# External_Camera_HAT_Connectors.net
KiCad netlist of a schematic drawn in Altium Designer
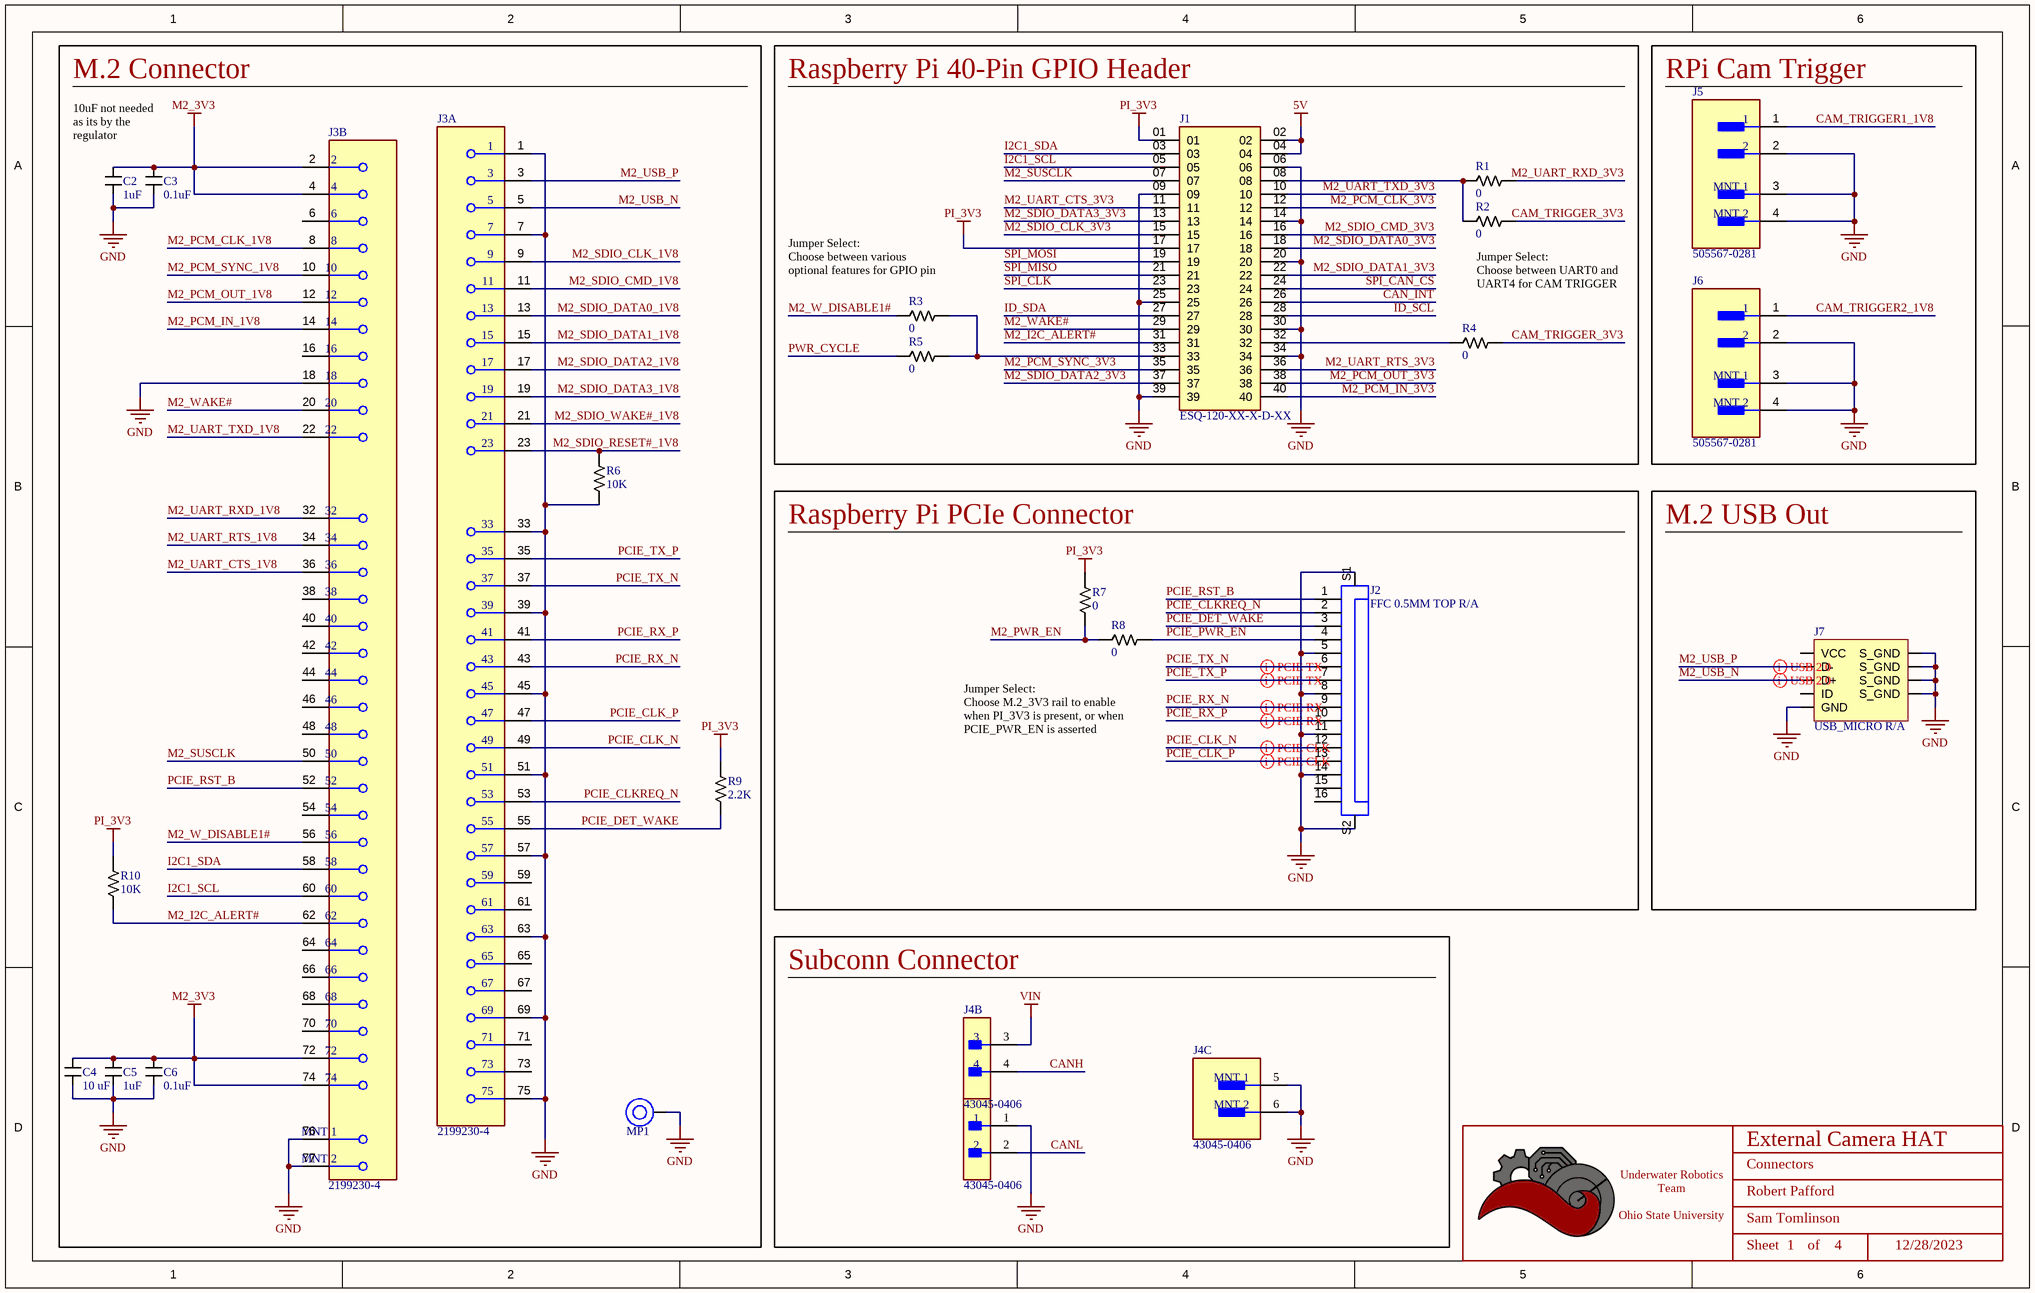
[diagram p0: External_Camera_HAT_Connectors.SchDoc]

(export (version "E")
  (design (tool "Eeschema 10.0.6"))
  (components
    (comp (ref "C2")
      (value "1uF")
      (footprint "CAPACITOR_0402")
      (description "Cap 1uF 16V +/-10%\r\nCeramic 0402")
      (fields
        (field (name "TOLERANCE") "+/- 10%")
        (field (name "VOLTAGE") "16V")
        (field (name "MADE BY") "Robert Pafford")
      )
      (libsource (lib "Capacitors") (part "CAPACITOR_1uF_0402"))
    )
    (comp (ref "C3")
      (value "0.1uF")
      (footprint "CAPACITOR_0402")
      (description "Cap 100nF 25V +/-10%\r\nCeramic 0402")
      (fields
        (field (name "TOLERANCE") "+/- 10%")
        (field (name "VOLTAGE") "25V")
        (field (name "MADE BY") "Robert Pafford")
      )
      (libsource (lib "Capacitors") (part "CAPACITOR_0.1uF_0402"))
    )
    (comp (ref "C4")
      (value "10uF Ceramic 6.3V")
      (footprint "CAPACITOR_0603")
      (description "Cap 10uF 6.3V +/-20%\r\nCeramic 0603")
      (fields
        (field (name "TOLERANCE") "+/- 20%")
        (field (name "VOLTAGE") "6.3V")
        (field (name "VALUE (UF)") "10 uF")
        (field (name "MADE BY") "Flip B")
      )
      (libsource (lib "Capacitors") (part "CAPACITOR_10uF_0603"))
    )
    (comp (ref "C5")
      (value "1uF")
      (footprint "CAPACITOR_0402")
      (description "Cap 1uF 16V +/-10%\r\nCeramic 0402")
      (fields
        (field (name "TOLERANCE") "+/- 10%")
        (field (name "VOLTAGE") "16V")
        (field (name "MADE BY") "Robert Pafford")
      )
      (libsource (lib "Capacitors") (part "CAPACITOR_1uF_0402"))
    )
    (comp (ref "C6")
      (value "0.1uF")
      (footprint "CAPACITOR_0402")
      (description "Cap 100nF 25V +/-10%\r\nCeramic 0402")
      (fields
        (field (name "TOLERANCE") "+/- 10%")
        (field (name "VOLTAGE") "25V")
        (field (name "MADE BY") "Robert Pafford")
      )
      (libsource (lib "Capacitors") (part "CAPACITOR_0.1uF_0402"))
    )
    (comp (ref "J1")
      (value "ESQ-120-XX-X-D-XX")
      (footprint "SAMTEC_ESQ-120-XX-X-D-XX")
      (description "ESQ - Samtec 2.54mm Elevated Dual Row Socket Strip 7.36mm Contact. 11.05mm Profile (13)")
      (fields (field (name "MP") "ESQ-120-13-L-D") (field (name "MF") "Samtec"))
      (libsource (lib "Connectors") (part "ESQ-120-XX-X-D-XX"))
    )
    (comp (ref "J2")
      (value "FFC 0.5MM TOP R/A")
      (footprint "FH12A-16S-0.5SH(55)")
      (description "16 Position FPC Connector Contacts, Top 0.02\" (0.5mm) Surface Mount, Right Angle, Gold Contacts")
      (fields (field (name "MADE BY") "Robert Pafford"))
      (libsource (lib "Connectors") (part "FFC_16POS_0.5MM_R/A_TOP"))
    )
    (comp (ref "J3")
      (value "2199230-4")
      (footprint "FP-2199230-4-MFG")
      (description "CONN FEMALE 67POS 0.020 GOLD")
      (fields
        (field (name "MANUFACTURER") "TE Connectivity")
        (field (name "OCTOPART") "https://octopart.com/2199230-4-te+connectivity-46436156")
      )
      (libsource (lib "Altium Content Vault") (part "6b4bc9aaecd91677fa565b830470f16"))
    )
    (comp (ref "J4")
      (value "43045-0406")
      (footprint "FP-43045-0406-MFG")
      (description "CONN HEADER SMD R/A 4POS 3MM")
      (libsource (lib "Altium Content Vault") (part "58585532e1459b3b5fa8464169874db"))
    )
    (comp (ref "J5")
      (value "505567-0281")
      (footprint "FP-505567-0281-MFG")
      (description "CONN HEADER SMD R/A 2POS 1.25MM")
      (libsource (lib "Altium Content Vault") (part "56ec3178a87b3978bdc1b3682cd516a"))
    )
    (comp (ref "J6")
      (value "505567-0281")
      (footprint "FP-505567-0281-MFG")
      (description "CONN HEADER SMD R/A 2POS 1.25MM")
      (libsource (lib "Altium Content Vault") (part "56ec3178a87b3978bdc1b3682cd516a"))
    )
    (comp (ref "J7")
      (value "USB_MICRO R/A")
      (footprint "CONN_MINIUSB")
      (description "Amphenol Micro USB-B\r\nUSB2.0 5 Pin Right Angle SMD")
      (fields (field (name "MANUFACTURER") "Amphenol") (field (name "CREATED BY") "Flip B"))
      (libsource (lib "Connectors") (part "CONN_MICROUSB"))
    )
    (comp (ref "MP1")
      (value "M3 x 2.5mm")
      (footprint "78614025360")
      (description "WE-SMSA SMT Spacer Studs Automotive, OD 6mm, ID 4.2mm, M3 x 2.5mm")
      (fields
        (field (name "MANUFACTURER PART NUMBER") "78614025360")
        (field (name "MANUFACTURER") "Wurth Elektronik")
      )
      (libsource (lib "Connectors") (part "M3_STANDOFF_78614025360"))
    )
    (comp (ref "R1")
      (value "0 Ohm 1% 1/16W")
      (footprint "RESISTOR_0402")
      (description "RES 0 OHM 1% 1/16W 0402")
      (fields
        (field (name "TOLERANCE") "+/- 1%")
        (field (name "VALUE  (OHMS)") "0")
        (field (name "MADE BY") "Robert Pafford")
      )
      (libsource (lib "Resistors") (part "RESISTOR_0_0402"))
    )
    (comp (ref "R2")
      (value "0 Ohm 1% 1/16W")
      (footprint "RESISTOR_0402")
      (description "RES 0 OHM 1% 1/16W 0402")
      (fields
        (field (name "TOLERANCE") "+/- 1%")
        (field (name "VALUE  (OHMS)") "0")
        (field (name "MADE BY") "Robert Pafford")
      )
      (libsource (lib "Resistors") (part "RESISTOR_0_0402"))
    )
    (comp (ref "R3")
      (value "0 Ohm 1% 1/16W")
      (footprint "RESISTOR_0402")
      (description "RES 0 OHM 1% 1/16W 0402")
      (fields
        (field (name "TOLERANCE") "+/- 1%")
        (field (name "VALUE  (OHMS)") "0")
        (field (name "MADE BY") "Robert Pafford")
      )
      (libsource (lib "Resistors") (part "RESISTOR_0_0402"))
    )
    (comp (ref "R4")
      (value "0 Ohm 1% 1/16W")
      (footprint "RESISTOR_0402")
      (description "RES 0 OHM 1% 1/16W 0402")
      (fields
        (field (name "TOLERANCE") "+/- 1%")
        (field (name "VALUE  (OHMS)") "0")
        (field (name "MADE BY") "Robert Pafford")
      )
      (libsource (lib "Resistors") (part "RESISTOR_0_0402"))
    )
    (comp (ref "R5")
      (value "0 Ohm 1% 1/16W")
      (footprint "RESISTOR_0402")
      (description "RES 0 OHM 1% 1/16W 0402")
      (fields
        (field (name "TOLERANCE") "+/- 1%")
        (field (name "VALUE  (OHMS)") "0")
        (field (name "MADE BY") "Robert Pafford")
      )
      (libsource (lib "Resistors") (part "RESISTOR_0_0402"))
    )
    (comp (ref "R6")
      (value "10k Ohm 1% 1/16W")
      (footprint "RESISTOR_0402")
      (description "RES 10k OHM 1% 1/16W 0402")
      (fields
        (field (name "TOLERANCE") "+/- 1%")
        (field (name "VALUE  (OHMS)") "10K")
        (field (name "MADE BY") "Robert Pafford")
      )
      (libsource (lib "Resistors") (part "RESISTOR_10K_0402"))
    )
    (comp (ref "R7")
      (value "0 Ohm 1% 1/16W")
      (footprint "RESISTOR_0402")
      (description "RES 0 OHM 1% 1/16W 0402")
      (fields
        (field (name "TOLERANCE") "+/- 1%")
        (field (name "VALUE  (OHMS)") "0")
        (field (name "MADE BY") "Robert Pafford")
      )
      (libsource (lib "Resistors") (part "RESISTOR_0_0402"))
    )
    (comp (ref "R8")
      (value "0 Ohm 1% 1/16W")
      (footprint "RESISTOR_0402")
      (description "RES 0 OHM 1% 1/16W 0402")
      (fields
        (field (name "TOLERANCE") "+/- 1%")
        (field (name "VALUE  (OHMS)") "0")
        (field (name "MADE BY") "Robert Pafford")
      )
      (libsource (lib "Resistors") (part "RESISTOR_0_0402"))
    )
    (comp (ref "R9")
      (value "2.2k Ohm 1% 1/16W")
      (footprint "RESISTOR_0402")
      (description "RES 2.2K OHM 1% 1/16W 0402")
      (fields
        (field (name "TOLERANCE") "+/- 1%")
        (field (name "VALUE  (OHMS)") "2.2K")
        (field (name "MADE BY") "Megan McCabe")
      )
      (libsource (lib "Resistors") (part "RESISTOR_2.2K_0402"))
    )
    (comp (ref "R10")
      (value "10k Ohm 1% 1/16W")
      (footprint "RESISTOR_0402")
      (description "RES 10k OHM 1% 1/16W 0402")
      (fields
        (field (name "TOLERANCE") "+/- 1%")
        (field (name "VALUE  (OHMS)") "10K")
        (field (name "MADE BY") "Robert Pafford")
      )
      (libsource (lib "Resistors") (part "RESISTOR_10K_0402"))
    )
  )
  (nets
    (net (code "1") (name "/CAM_TRIGGER1_1V8") (class "Default")
      (node (ref "J5") (pin "1") (pinfunction "1_1") (pintype "passive"))
    )
    (net (code "2") (name "/CAM_TRIGGER2_1V8") (class "Default")
      (node (ref "J6") (pin "1") (pinfunction "1_1") (pintype "passive"))
    )
    (net (code "3") (name "/CAM_TRIGGER_3V3") (class "Default")
      (node (ref "R2") (pin "1") (pinfunction "1_1") (pintype "passive"))
      (node (ref "R4") (pin "1") (pinfunction "1_1") (pintype "passive"))
    )
    (net (code "4") (name "/CANH") (class "Default")
      (node (ref "J4") (pin "4") (pinfunction "4_4") (pintype "passive"))
    )
    (net (code "5") (name "/CANL") (class "Default")
      (node (ref "J4") (pin "2") (pinfunction "2_2") (pintype "passive"))
    )
    (net (code "6") (name "/CAN_INT") (class "Default")
      (node (ref "J1") (pin "26") (pinfunction "26_26") (pintype "passive"))
    )
    (net (code "7") (name "/I2C1_SCL") (class "Default")
      (node (ref "J1") (pin "05") (pinfunction "05_05") (pintype "passive"))
      (node (ref "J3") (pin "60") (pinfunction "60_60") (pintype "passive"))
    )
    (net (code "8") (name "/I2C1_SDA") (class "Default")
      (node (ref "J1") (pin "03") (pinfunction "03_03") (pintype "passive"))
      (node (ref "J3") (pin "58") (pinfunction "58_58") (pintype "passive"))
    )
    (net (code "9") (name "/ID_SCL") (class "Default")
      (node (ref "J1") (pin "28") (pinfunction "28_28") (pintype "passive"))
    )
    (net (code "10") (name "/ID_SDA") (class "Default")
      (node (ref "J1") (pin "27") (pinfunction "27_27") (pintype "passive"))
    )
    (net (code "11") (name "/M2_I2C_ALERT#") (class "Default")
      (node (ref "J1") (pin "31") (pinfunction "31_31") (pintype "passive"))
      (node (ref "J3") (pin "62") (pinfunction "62_62") (pintype "passive"))
      (node (ref "R10") (pin "2") (pinfunction "2_2") (pintype "passive"))
    )
    (net (code "12") (name "/M2_PCM_CLK_1V8") (class "Default")
      (node (ref "J3") (pin "8") (pinfunction "8_8") (pintype "passive"))
    )
    (net (code "13") (name "/M2_PCM_CLK_3V3") (class "Default")
      (node (ref "J1") (pin "12") (pinfunction "12_12") (pintype "passive"))
    )
    (net (code "14") (name "/M2_PCM_IN_1V8") (class "Default")
      (node (ref "J3") (pin "14") (pinfunction "14_14") (pintype "passive"))
    )
    (net (code "15") (name "/M2_PCM_IN_3V3") (class "Default")
      (node (ref "J1") (pin "40") (pinfunction "40_40") (pintype "passive"))
    )
    (net (code "16") (name "/M2_PCM_OUT_1V8") (class "Default")
      (node (ref "J3") (pin "12") (pinfunction "12_12") (pintype "passive"))
    )
    (net (code "17") (name "/M2_PCM_OUT_3V3") (class "Default")
      (node (ref "J1") (pin "38") (pinfunction "38_38") (pintype "passive"))
    )
    (net (code "18") (name "/M2_PCM_SYNC_1V8") (class "Default")
      (node (ref "J3") (pin "10") (pinfunction "10_10") (pintype "passive"))
    )
    (net (code "19") (name "/M2_PCM_SYNC_3V3") (class "Default")
      (node (ref "J1") (pin "35") (pinfunction "35_35") (pintype "passive"))
    )
    (net (code "20") (name "/M2_PWR_EN") (class "Default")
      (node (ref "R7") (pin "2") (pinfunction "2_2") (pintype "passive"))
      (node (ref "R8") (pin "2") (pinfunction "2_2") (pintype "passive"))
    )
    (net (code "21") (name "/M2_SDIO_CLK_1V8") (class "Default")
      (node (ref "J3") (pin "9") (pinfunction "9_9") (pintype "passive"))
    )
    (net (code "22") (name "/M2_SDIO_CLK_3V3") (class "Default")
      (node (ref "J1") (pin "15") (pinfunction "15_15") (pintype "passive"))
    )
    (net (code "23") (name "/M2_SDIO_CMD_1V8") (class "Default")
      (node (ref "J3") (pin "11") (pinfunction "11_11") (pintype "passive"))
    )
    (net (code "24") (name "/M2_SDIO_CMD_3V3") (class "Default")
      (node (ref "J1") (pin "16") (pinfunction "16_16") (pintype "passive"))
    )
    (net (code "25") (name "/M2_SDIO_DATA0_1V8") (class "Default")
      (node (ref "J3") (pin "13") (pinfunction "13_13") (pintype "passive"))
    )
    (net (code "26") (name "/M2_SDIO_DATA0_3V3") (class "Default")
      (node (ref "J1") (pin "18") (pinfunction "18_18") (pintype "passive"))
    )
    (net (code "27") (name "/M2_SDIO_DATA1_1V8") (class "Default")
      (node (ref "J3") (pin "15") (pinfunction "15_15") (pintype "passive"))
    )
    (net (code "28") (name "/M2_SDIO_DATA1_3V3") (class "Default")
      (node (ref "J1") (pin "22") (pinfunction "22_22") (pintype "passive"))
    )
    (net (code "29") (name "/M2_SDIO_DATA2_1V8") (class "Default")
      (node (ref "J3") (pin "17") (pinfunction "17_17") (pintype "passive"))
    )
    (net (code "30") (name "/M2_SDIO_DATA2_3V3") (class "Default")
      (node (ref "J1") (pin "37") (pinfunction "37_37") (pintype "passive"))
    )
    (net (code "31") (name "/M2_SDIO_DATA3_1V8") (class "Default")
      (node (ref "J3") (pin "19") (pinfunction "19_19") (pintype "passive"))
    )
    (net (code "32") (name "/M2_SDIO_DATA3_3V3") (class "Default")
      (node (ref "J1") (pin "13") (pinfunction "13_13") (pintype "passive"))
    )
    (net (code "33") (name "/M2_SDIO_RESET#_1V8") (class "Default")
      (node (ref "J3") (pin "23") (pinfunction "23_23") (pintype "passive"))
      (node (ref "R6") (pin "1") (pinfunction "1_1") (pintype "passive"))
    )
    (net (code "34") (name "/M2_SDIO_WAKE#_1V8") (class "Default")
      (node (ref "J3") (pin "21") (pinfunction "21_21") (pintype "passive"))
    )
    (net (code "35") (name "/M2_SUSCLK") (class "Default")
      (node (ref "J1") (pin "07") (pinfunction "07_07") (pintype "passive"))
      (node (ref "J3") (pin "50") (pinfunction "50_50") (pintype "passive"))
    )
    (net (code "36") (name "/M2_UART_CTS_1V8") (class "Default")
      (node (ref "J3") (pin "36") (pinfunction "36_36") (pintype "passive"))
    )
    (net (code "37") (name "/M2_UART_CTS_3V3") (class "Default")
      (node (ref "J1") (pin "11") (pinfunction "11_11") (pintype "passive"))
    )
    (net (code "38") (name "/M2_UART_RTS_1V8") (class "Default")
      (node (ref "J3") (pin "34") (pinfunction "34_34") (pintype "passive"))
    )
    (net (code "39") (name "/M2_UART_RTS_3V3") (class "Default")
      (node (ref "J1") (pin "36") (pinfunction "36_36") (pintype "passive"))
    )
    (net (code "40") (name "/M2_UART_RXD_1V8") (class "Default")
      (node (ref "J3") (pin "32") (pinfunction "32_32") (pintype "passive"))
    )
    (net (code "41") (name "/M2_UART_RXD_3V3") (class "Default")
      (node (ref "R1") (pin "1") (pinfunction "1_1") (pintype "passive"))
    )
    (net (code "42") (name "/M2_UART_TXD_1V8") (class "Default")
      (node (ref "J3") (pin "22") (pinfunction "22_22") (pintype "passive"))
    )
    (net (code "43") (name "/M2_UART_TXD_3V3") (class "Default")
      (node (ref "J1") (pin "10") (pinfunction "10_10") (pintype "passive"))
    )
    (net (code "44") (name "/M2_USB_N") (class "Default")
      (node (ref "J3") (pin "5") (pinfunction "5_5") (pintype "passive"))
      (node (ref "J7") (pin "3") (pinfunction "D+_3") (pintype "passive"))
    )
    (net (code "45") (name "/M2_USB_P") (class "Default")
      (node (ref "J3") (pin "3") (pinfunction "3_3") (pintype "passive"))
      (node (ref "J7") (pin "2") (pinfunction "D-_2") (pintype "passive"))
    )
    (net (code "46") (name "/M2_WAKE#") (class "Default")
      (node (ref "J1") (pin "29") (pinfunction "29_29") (pintype "passive"))
      (node (ref "J3") (pin "20") (pinfunction "20_20") (pintype "passive"))
    )
    (net (code "47") (name "/M2_W_DISABLE1#") (class "Default")
      (node (ref "J3") (pin "56") (pinfunction "56_56") (pintype "passive"))
      (node (ref "R3") (pin "2") (pinfunction "2_2") (pintype "passive"))
    )
    (net (code "48") (name "/PCIE_CLKREQ_N") (class "Default")
      (node (ref "J2") (pin "2") (pinfunction "2_2") (pintype "passive"))
      (node (ref "J3") (pin "53") (pinfunction "53_53") (pintype "passive"))
    )
    (net (code "49") (name "/PCIE_CLK_N") (class "Default")
      (node (ref "J2") (pin "12") (pinfunction "12_12") (pintype "passive"))
      (node (ref "J3") (pin "49") (pinfunction "49_49") (pintype "passive"))
    )
    (net (code "50") (name "/PCIE_CLK_P") (class "Default")
      (node (ref "J2") (pin "13") (pinfunction "13_13") (pintype "passive"))
      (node (ref "J3") (pin "47") (pinfunction "47_47") (pintype "passive"))
    )
    (net (code "51") (name "/PCIE_DET_WAKE") (class "Default")
      (node (ref "J2") (pin "3") (pinfunction "3_3") (pintype "passive"))
      (node (ref "J3") (pin "55") (pinfunction "55_55") (pintype "passive"))
      (node (ref "R9") (pin "2") (pinfunction "2_2") (pintype "passive"))
    )
    (net (code "52") (name "/PCIE_PWR_EN") (class "Default")
      (node (ref "J2") (pin "4") (pinfunction "4_4") (pintype "passive"))
      (node (ref "R8") (pin "1") (pinfunction "1_1") (pintype "passive"))
    )
    (net (code "53") (name "/PCIE_RST_B") (class "Default")
      (node (ref "J2") (pin "1") (pinfunction "1_1") (pintype "passive"))
      (node (ref "J3") (pin "52") (pinfunction "52_52") (pintype "passive"))
    )
    (net (code "54") (name "/PCIE_RX_N") (class "Default")
      (node (ref "J2") (pin "9") (pinfunction "9_9") (pintype "passive"))
      (node (ref "J3") (pin "43") (pinfunction "43_43") (pintype "passive"))
    )
    (net (code "55") (name "/PCIE_RX_P") (class "Default")
      (node (ref "J2") (pin "10") (pinfunction "10_10") (pintype "passive"))
      (node (ref "J3") (pin "41") (pinfunction "41_41") (pintype "passive"))
    )
    (net (code "56") (name "/PCIE_TX_N") (class "Default")
      (node (ref "J2") (pin "6") (pinfunction "6_6") (pintype "passive"))
      (node (ref "J3") (pin "37") (pinfunction "37_37") (pintype "passive"))
    )
    (net (code "57") (name "/PCIE_TX_P") (class "Default")
      (node (ref "J2") (pin "7") (pinfunction "7_7") (pintype "passive"))
      (node (ref "J3") (pin "35") (pinfunction "35_35") (pintype "passive"))
    )
    (net (code "58") (name "/PWR_CYCLE") (class "Default")
      (node (ref "R5") (pin "2") (pinfunction "2_2") (pintype "passive"))
    )
    (net (code "59") (name "/SPI_CAN_CS") (class "Default")
      (node (ref "J1") (pin "24") (pinfunction "24_24") (pintype "passive"))
    )
    (net (code "60") (name "/SPI_CLK") (class "Default")
      (node (ref "J1") (pin "23") (pinfunction "23_23") (pintype "passive"))
    )
    (net (code "61") (name "/SPI_MISO") (class "Default")
      (node (ref "J1") (pin "21") (pinfunction "21_21") (pintype "passive"))
    )
    (net (code "62") (name "/SPI_MOSI") (class "Default")
      (node (ref "J1") (pin "19") (pinfunction "19_19") (pintype "passive"))
    )
    (net (code "63") (name "5V") (class "Default")
      (node (ref "J1") (pin "02") (pinfunction "02_02") (pintype "passive"))
      (node (ref "J1") (pin "04") (pinfunction "04_04") (pintype "passive"))
    )
    (net (code "64") (name "GND") (class "Default")
      (node (ref "C2") (pin "2") (pinfunction "2_2") (pintype "passive"))
      (node (ref "C3") (pin "2") (pinfunction "2_2") (pintype "passive"))
      (node (ref "C4") (pin "2") (pinfunction "2_2") (pintype "passive"))
      (node (ref "C5") (pin "2") (pinfunction "2_2") (pintype "passive"))
      (node (ref "C6") (pin "2") (pinfunction "2_2") (pintype "passive"))
      (node (ref "J1") (pin "06") (pinfunction "06_06") (pintype "passive"))
      (node (ref "J1") (pin "09") (pinfunction "09_09") (pintype "passive"))
      (node (ref "J1") (pin "14") (pinfunction "14_14") (pintype "passive"))
      (node (ref "J1") (pin "20") (pinfunction "20_20") (pintype "passive"))
      (node (ref "J1") (pin "25") (pinfunction "25_25") (pintype "passive"))
      (node (ref "J1") (pin "30") (pinfunction "30_30") (pintype "passive"))
      (node (ref "J1") (pin "34") (pinfunction "34_34") (pintype "passive"))
      (node (ref "J1") (pin "39") (pinfunction "39_39") (pintype "passive"))
      (node (ref "J2") (pin "11") (pinfunction "11_11") (pintype "passive"))
      (node (ref "J2") (pin "14") (pinfunction "14_14") (pintype "passive"))
      (node (ref "J2") (pin "5") (pinfunction "5_5") (pintype "passive"))
      (node (ref "J2") (pin "8") (pinfunction "8_8") (pintype "passive"))
      (node (ref "J2") (pin "S1") (pinfunction "S1_S1") (pintype "passive"))
      (node (ref "J2") (pin "S2") (pinfunction "S2_S2") (pintype "passive"))
      (node (ref "J3") (pin "1") (pinfunction "1_1") (pintype "passive"))
      (node (ref "J3") (pin "18") (pinfunction "18_18") (pintype "passive"))
      (node (ref "J3") (pin "33") (pinfunction "33_33") (pintype "passive"))
      (node (ref "J3") (pin "39") (pinfunction "39_39") (pintype "passive"))
      (node (ref "J3") (pin "45") (pinfunction "45_45") (pintype "passive"))
      (node (ref "J3") (pin "51") (pinfunction "51_51") (pintype "passive"))
      (node (ref "J3") (pin "57") (pinfunction "57_57") (pintype "passive"))
      (node (ref "J3") (pin "63") (pinfunction "63_63") (pintype "passive"))
      (node (ref "J3") (pin "69") (pinfunction "69_69") (pintype "passive"))
      (node (ref "J3") (pin "7") (pinfunction "7_7") (pintype "passive"))
      (node (ref "J3") (pin "75") (pinfunction "75_75") (pintype "passive"))
      (node (ref "J3") (pin "76") (pinfunction "MNT_1_76") (pintype "passive"))
      (node (ref "J3") (pin "77") (pinfunction "MNT_2_77") (pintype "passive"))
      (node (ref "J4") (pin "1") (pinfunction "1_1") (pintype "passive"))
      (node (ref "J4") (pin "5") (pinfunction "MNT_1_5") (pintype "passive"))
      (node (ref "J4") (pin "6") (pinfunction "MNT_2_6") (pintype "passive"))
      (node (ref "J5") (pin "2") (pinfunction "2_2") (pintype "passive"))
      (node (ref "J5") (pin "3") (pinfunction "MNT_1_3") (pintype "passive"))
      (node (ref "J5") (pin "4") (pinfunction "MNT_2_4") (pintype "passive"))
      (node (ref "J6") (pin "2") (pinfunction "2_2") (pintype "passive"))
      (node (ref "J6") (pin "3") (pinfunction "MNT_1_3") (pintype "passive"))
      (node (ref "J6") (pin "4") (pinfunction "MNT_2_4") (pintype "passive"))
      (node (ref "J7") (pin "5") (pinfunction "GND_5") (pintype "passive"))
      (node (ref "J7") (pin "6") (pinfunction "S_GND_6") (pintype "passive"))
      (node (ref "J7") (pin "7") (pinfunction "S_GND_7") (pintype "passive"))
      (node (ref "J7") (pin "8") (pinfunction "S_GND_8") (pintype "passive"))
      (node (ref "J7") (pin "9") (pinfunction "S_GND_9") (pintype "passive"))
      (node (ref "MP1") (pin "1") (pinfunction "1_1") (pintype "passive"))
      (node (ref "R6") (pin "2") (pinfunction "2_2") (pintype "passive"))
    )
    (net (code "65") (name "M2_3V3") (class "Default")
      (node (ref "C2") (pin "1") (pinfunction "1_1") (pintype "passive"))
      (node (ref "C3") (pin "1") (pinfunction "1_1") (pintype "passive"))
      (node (ref "C4") (pin "1") (pinfunction "1_1") (pintype "passive"))
      (node (ref "C5") (pin "1") (pinfunction "1_1") (pintype "passive"))
      (node (ref "C6") (pin "1") (pinfunction "1_1") (pintype "passive"))
      (node (ref "J3") (pin "2") (pinfunction "2_2") (pintype "passive"))
      (node (ref "J3") (pin "4") (pinfunction "4_4") (pintype "passive"))
      (node (ref "J3") (pin "72") (pinfunction "72_72") (pintype "passive"))
      (node (ref "J3") (pin "74") (pinfunction "74_74") (pintype "passive"))
    )
    (net (code "66") (name "Net-(J1-Pad08)") (class "Default")
      (node (ref "J1") (pin "08") (pinfunction "08_08") (pintype "passive"))
      (node (ref "R1") (pin "2") (pinfunction "2_2") (pintype "passive"))
      (node (ref "R2") (pin "2") (pinfunction "2_2") (pintype "passive"))
    )
    (net (code "67") (name "Net-(J1-Pad32)") (class "Default")
      (node (ref "J1") (pin "32") (pinfunction "32_32") (pintype "passive"))
      (node (ref "R4") (pin "2") (pinfunction "2_2") (pintype "passive"))
    )
    (net (code "68") (name "Net-(J1-Pad33)") (class "Default")
      (node (ref "J1") (pin "33") (pinfunction "33_33") (pintype "passive"))
      (node (ref "R3") (pin "1") (pinfunction "1_1") (pintype "passive"))
      (node (ref "R5") (pin "1") (pinfunction "1_1") (pintype "passive"))
    )
    (net (code "69") (name "PI_3V3") (class "Default")
      (node (ref "J1") (pin "01") (pinfunction "01_01") (pintype "passive"))
      (node (ref "J1") (pin "17") (pinfunction "17_17") (pintype "passive"))
      (node (ref "R10") (pin "1") (pinfunction "1_1") (pintype "passive"))
      (node (ref "R7") (pin "1") (pinfunction "1_1") (pintype "passive"))
      (node (ref "R9") (pin "1") (pinfunction "1_1") (pintype "passive"))
    )
    (net (code "70") (name "VIN") (class "Default")
      (node (ref "J4") (pin "3") (pinfunction "3_3") (pintype "passive"))
    )
    (net (code "71") (name "unconnected-(J2-Pad15)") (class "Default")
      (node (ref "J2") (pin "15") (pinfunction "15_15") (pintype "passive"))
    )
    (net (code "72") (name "unconnected-(J2-Pad16)") (class "Default")
      (node (ref "J2") (pin "16") (pinfunction "16_16") (pintype "passive"))
    )
    (net (code "73") (name "unconnected-(J3-Pad6)") (class "Default")
      (node (ref "J3") (pin "6") (pinfunction "6_6") (pintype "passive"))
    )
    (net (code "74") (name "unconnected-(J3-Pad16)") (class "Default")
      (node (ref "J3") (pin "16") (pinfunction "16_16") (pintype "passive"))
    )
    (net (code "75") (name "unconnected-(J3-Pad38)") (class "Default")
      (node (ref "J3") (pin "38") (pinfunction "38_38") (pintype "passive"))
    )
    (net (code "76") (name "unconnected-(J3-Pad40)") (class "Default")
      (node (ref "J3") (pin "40") (pinfunction "40_40") (pintype "passive"))
    )
    (net (code "77") (name "unconnected-(J3-Pad42)") (class "Default")
      (node (ref "J3") (pin "42") (pinfunction "42_42") (pintype "passive"))
    )
    (net (code "78") (name "unconnected-(J3-Pad44)") (class "Default")
      (node (ref "J3") (pin "44") (pinfunction "44_44") (pintype "passive"))
    )
    (net (code "79") (name "unconnected-(J3-Pad46)") (class "Default")
      (node (ref "J3") (pin "46") (pinfunction "46_46") (pintype "passive"))
    )
    (net (code "80") (name "unconnected-(J3-Pad48)") (class "Default")
      (node (ref "J3") (pin "48") (pinfunction "48_48") (pintype "passive"))
    )
    (net (code "81") (name "unconnected-(J3-Pad54)") (class "Default")
      (node (ref "J3") (pin "54") (pinfunction "54_54") (pintype "passive"))
    )
    (net (code "82") (name "unconnected-(J3-Pad59)") (class "Default")
      (node (ref "J3") (pin "59") (pinfunction "59_59") (pintype "passive"))
    )
    (net (code "83") (name "unconnected-(J3-Pad61)") (class "Default")
      (node (ref "J3") (pin "61") (pinfunction "61_61") (pintype "passive"))
    )
    (net (code "84") (name "unconnected-(J3-Pad64)") (class "Default")
      (node (ref "J3") (pin "64") (pinfunction "64_64") (pintype "passive"))
    )
    (net (code "85") (name "unconnected-(J3-Pad65)") (class "Default")
      (node (ref "J3") (pin "65") (pinfunction "65_65") (pintype "passive"))
    )
    (net (code "86") (name "unconnected-(J3-Pad66)") (class "Default")
      (node (ref "J3") (pin "66") (pinfunction "66_66") (pintype "passive"))
    )
    (net (code "87") (name "unconnected-(J3-Pad67)") (class "Default")
      (node (ref "J3") (pin "67") (pinfunction "67_67") (pintype "passive"))
    )
    (net (code "88") (name "unconnected-(J3-Pad68)") (class "Default")
      (node (ref "J3") (pin "68") (pinfunction "68_68") (pintype "passive"))
    )
    (net (code "89") (name "unconnected-(J3-Pad70)") (class "Default")
      (node (ref "J3") (pin "70") (pinfunction "70_70") (pintype "passive"))
    )
    (net (code "90") (name "unconnected-(J3-Pad71)") (class "Default")
      (node (ref "J3") (pin "71") (pinfunction "71_71") (pintype "passive"))
    )
    (net (code "91") (name "unconnected-(J3-Pad73)") (class "Default")
      (node (ref "J3") (pin "73") (pinfunction "73_73") (pintype "passive"))
    )
    (net (code "92") (name "unconnected-(J7-ID-Pad4)") (class "Default")
      (node (ref "J7") (pin "4") (pinfunction "ID_4") (pintype "passive"))
    )
    (net (code "93") (name "unconnected-(J7-VCC-Pad1)") (class "Default")
      (node (ref "J7") (pin "1") (pinfunction "VCC_1") (pintype "passive"))
    )
  )
)
